# BT.net
KiCad netlist of a schematic drawn in Altium Designer
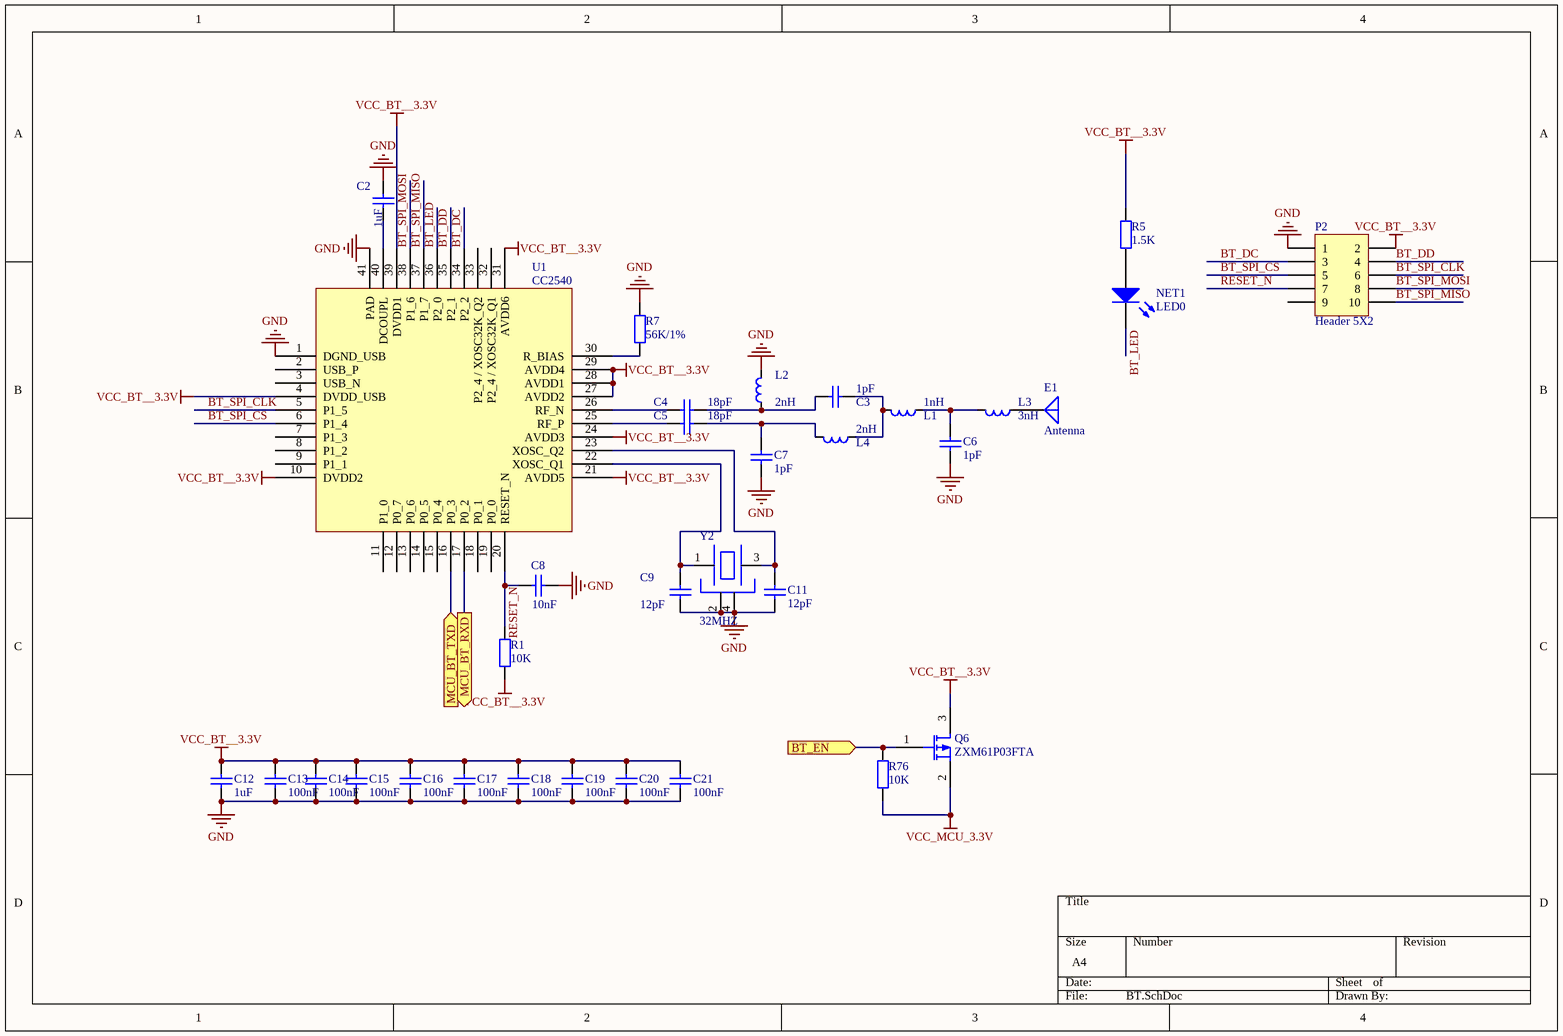
[diagram p0: BT.SchDoc]

(export (version "E")
  (design (tool "Eeschema 10.0.6"))
  (components
    (comp (ref "C2")
      (value "1uF")
      (footprint "0603C")
      (description "Capacitor")
      (fields (field (name "PUBLISHER") "Altium Limited"))
      (libsource (lib "Miscellaneous Devices") (part "Cap"))
    )
    (comp (ref "C3")
      (value "1pF")
      (footprint "0402C")
      (description "Capacitor")
      (fields (field (name "PUBLISHER") "Altium Limited"))
      (libsource (lib "Miscellaneous Devices") (part "Cap"))
    )
    (comp (ref "C4")
      (value "18pF")
      (footprint "0402C")
      (description "Capacitor")
      (fields (field (name "PUBLISHER") "Altium Limited"))
      (libsource (lib "Miscellaneous Devices") (part "Cap"))
    )
    (comp (ref "C5")
      (value "18pF")
      (footprint "0402C")
      (description "Capacitor")
      (fields (field (name "PUBLISHER") "Altium Limited"))
      (libsource (lib "Miscellaneous Devices") (part "Cap"))
    )
    (comp (ref "C6")
      (value "1pF")
      (footprint "0402C")
      (description "Capacitor")
      (fields (field (name "PUBLISHER") "Altium Limited"))
      (libsource (lib "Miscellaneous Devices") (part "Cap"))
    )
    (comp (ref "C7")
      (value "1pF")
      (footprint "0402C")
      (description "Capacitor")
      (fields (field (name "PUBLISHER") "Altium Limited"))
      (libsource (lib "Miscellaneous Devices") (part "Cap"))
    )
    (comp (ref "C8")
      (value "10nF")
      (footprint "0402C")
      (description "Capacitor")
      (fields (field (name "PUBLISHER") "Altium Limited"))
      (libsource (lib "Miscellaneous Devices") (part "Cap"))
    )
    (comp (ref "C9")
      (value "12pF")
      (footprint "0402C")
      (description "Capacitor")
      (fields (field (name "PUBLISHER") "Altium Limited"))
      (libsource (lib "Miscellaneous Devices") (part "Cap"))
    )
    (comp (ref "C11")
      (value "12pF")
      (footprint "0402C")
      (description "Capacitor")
      (fields (field (name "PUBLISHER") "Altium Limited"))
      (libsource (lib "Miscellaneous Devices") (part "Cap"))
    )
    (comp (ref "C12")
      (value "1uF")
      (footprint "0603C")
      (description "Capacitor")
      (fields (field (name "PUBLISHER") "Altium Limited"))
      (libsource (lib "Miscellaneous Devices") (part "Cap"))
    )
    (comp (ref "C13")
      (value "100nF")
      (footprint "0603C")
      (description "Capacitor")
      (fields (field (name "PUBLISHER") "Altium Limited"))
      (libsource (lib "Miscellaneous Devices") (part "Cap"))
    )
    (comp (ref "C14")
      (value "100nF")
      (footprint "0603C")
      (description "Capacitor")
      (fields (field (name "PUBLISHER") "Altium Limited"))
      (libsource (lib "Miscellaneous Devices") (part "Cap"))
    )
    (comp (ref "C15")
      (value "100nF")
      (footprint "0603C")
      (description "Capacitor")
      (fields (field (name "PUBLISHER") "Altium Limited"))
      (libsource (lib "Miscellaneous Devices") (part "Cap"))
    )
    (comp (ref "C16")
      (value "100nF")
      (footprint "0603C")
      (description "Capacitor")
      (fields (field (name "PUBLISHER") "Altium Limited"))
      (libsource (lib "Miscellaneous Devices") (part "Cap"))
    )
    (comp (ref "C17")
      (value "100nF")
      (footprint "0603C")
      (description "Capacitor")
      (fields (field (name "PUBLISHER") "Altium Limited"))
      (libsource (lib "Miscellaneous Devices") (part "Cap"))
    )
    (comp (ref "C18")
      (value "100nF")
      (footprint "0603C")
      (description "Capacitor")
      (fields (field (name "PUBLISHER") "Altium Limited"))
      (libsource (lib "Miscellaneous Devices") (part "Cap"))
    )
    (comp (ref "C19")
      (value "100nF")
      (footprint "0603C")
      (description "Capacitor")
      (fields (field (name "PUBLISHER") "Altium Limited"))
      (libsource (lib "Miscellaneous Devices") (part "Cap"))
    )
    (comp (ref "C20")
      (value "100nF")
      (footprint "0603C")
      (description "Capacitor")
      (fields (field (name "PUBLISHER") "Altium Limited"))
      (libsource (lib "Miscellaneous Devices") (part "Cap"))
    )
    (comp (ref "C21")
      (value "100nF")
      (footprint "0603C")
      (description "Capacitor")
      (fields (field (name "PUBLISHER") "Altium Limited"))
      (libsource (lib "Miscellaneous Devices") (part "Cap"))
    )
    (comp (ref "E1")
      (value "Antenna")
      (footprint "AN2051")
      (description "Generic Antenna")
      (fields (field (name "PUBLISHER") "Altium Limited"))
      (libsource (lib "Miscellaneous Devices") (part "Antenna"))
    )
    (comp (ref "L1") (value "1nH") (footprint "0402R") (description "L") (libsource (lib "") (part "L_4_1")))
    (comp (ref "L2") (value "2nH") (footprint "0402R") (description "L") (libsource (lib "*") (part "L_4")))
    (comp (ref "L3") (value "3nH") (footprint "0402R") (description "L") (libsource (lib "") (part "L_4_1")))
    (comp (ref "L4") (value "2nH") (footprint "0402R") (description "L") (libsource (lib "") (part "L_4_1")))
    (comp (ref "NET1")
      (value "LED0")
      (footprint "0603LED")
      (description "Typical INFRARED GaAs LED")
      (fields (field (name "PUBLISHER") "Altium Limited"))
      (libsource (lib "Miscellaneous Devices") (part "LED0"))
    )
    (comp (ref "P2")
      (value "Header 5X2")
      (footprint "HDR2X5")
      (description "Header, 5-Pin, Dual row")
      (fields (field (name "PUBLISHER") "Altium Limited"))
      (libsource (lib "Miscellaneous Connectors") (part "Header 5X2"))
    )
    (comp (ref "Q6")
      (value "ZXM61P03FTA")
      (footprint "SOT23-3")
      (description "ZXM61P03F")
      (fields (field (name "PUBLISHER") "Altium Limited"))
      (libsource (lib "Miscellaneous Devices") (part "MOSFET-P"))
    )
    (comp (ref "R1")
      (value "10K")
      (footprint "0603R")
      (description "Resistor")
      (fields (field (name "PUBLISHER") "Altium Limited"))
      (libsource (lib "Miscellaneous Devices") (part "Res2"))
    )
    (comp (ref "R5")
      (value "1.5K")
      (footprint "0603R")
      (description "Resistor")
      (fields (field (name "PUBLISHER") "Altium Limited"))
      (libsource (lib "Miscellaneous Devices") (part "Res2"))
    )
    (comp (ref "R7")
      (value "56K/1%")
      (footprint "0603R")
      (description "Resistor")
      (fields (field (name "PUBLISHER") "Altium Limited"))
      (libsource (lib "Miscellaneous Devices") (part "Res2"))
    )
    (comp (ref "R76")
      (value "10K")
      (footprint "0603R")
      (description "Resistor")
      (fields (field (name "PUBLISHER") "Altium Limited"))
      (libsource (lib "Miscellaneous Devices") (part "Res2"))
    )
    (comp (ref "U1")
      (value "CC2540")
      (footprint "QFN50P600X600X80-40N")
      (libsource (lib "stm32") (part "CC2540"))
    )
    (comp (ref "Y2")
      (value "32MHZ")
      (footprint "OSCILLATOR-3.2X2.5")
      (libsource (lib "Myself_1") (part "XTAL3"))
    )
  )
  (nets
    (net (code "1") (name "/BT_DC") (class "Default")
      (node (ref "P2") (pin "3") (pinfunction "3_3") (pintype "passive"))
      (node (ref "U1") (pin "34") (pinfunction "P2_2_34") (pintype "passive"))
    )
    (net (code "2") (name "/BT_DD") (class "Default")
      (node (ref "P2") (pin "4") (pinfunction "4_4") (pintype "passive"))
      (node (ref "U1") (pin "35") (pinfunction "P2_1_35") (pintype "passive"))
    )
    (net (code "3") (name "/BT_EN") (class "Default")
      (node (ref "Q6") (pin "1") (pinfunction "G_1") (pintype "passive"))
      (node (ref "R76") (pin "1") (pinfunction "1_1") (pintype "passive"))
    )
    (net (code "4") (name "/BT_LED") (class "Default")
      (node (ref "NET1") (pin "2") (pinfunction "K_2") (pintype "passive"))
      (node (ref "U1") (pin "36") (pinfunction "P2_0_36") (pintype "passive"))
    )
    (net (code "5") (name "/BT_SPI_CLK") (class "Default")
      (node (ref "P2") (pin "6") (pinfunction "6_6") (pintype "passive"))
      (node (ref "U1") (pin "5") (pinfunction "P1_5_5") (pintype "passive"))
    )
    (net (code "6") (name "/BT_SPI_CS") (class "Default")
      (node (ref "P2") (pin "5") (pinfunction "5_5") (pintype "passive"))
      (node (ref "U1") (pin "6") (pinfunction "P1_4_6") (pintype "passive"))
    )
    (net (code "7") (name "/BT_SPI_MISO") (class "Default")
      (node (ref "P2") (pin "10") (pinfunction "10_10") (pintype "passive"))
      (node (ref "U1") (pin "37") (pinfunction "P1_7_37") (pintype "passive"))
    )
    (net (code "8") (name "/BT_SPI_MOSI") (class "Default")
      (node (ref "P2") (pin "8") (pinfunction "8_8") (pintype "passive"))
      (node (ref "U1") (pin "38") (pinfunction "P1_6_38") (pintype "passive"))
    )
    (net (code "9") (name "/MCU_BT_RXD") (class "Default")
      (node (ref "U1") (pin "17") (pinfunction "P0_2_17") (pintype "passive"))
    )
    (net (code "10") (name "/MCU_BT_TXD") (class "Default")
      (node (ref "U1") (pin "16") (pinfunction "P0_3_16") (pintype "passive"))
    )
    (net (code "11") (name "/RESET_N") (class "Default")
      (node (ref "C8") (pin "2") (pinfunction "2_2") (pintype "passive"))
      (node (ref "P2") (pin "7") (pinfunction "7_7") (pintype "passive"))
      (node (ref "R1") (pin "1") (pinfunction "1_1") (pintype "passive"))
      (node (ref "U1") (pin "20") (pinfunction "RESET_N_20") (pintype "passive"))
    )
    (net (code "12") (name "GND") (class "Default")
      (node (ref "C11") (pin "1") (pinfunction "1_1") (pintype "passive"))
      (node (ref "C12") (pin "2") (pinfunction "2_2") (pintype "passive"))
      (node (ref "C13") (pin "2") (pinfunction "2_2") (pintype "passive"))
      (node (ref "C14") (pin "2") (pinfunction "2_2") (pintype "passive"))
      (node (ref "C15") (pin "2") (pinfunction "2_2") (pintype "passive"))
      (node (ref "C16") (pin "2") (pinfunction "2_2") (pintype "passive"))
      (node (ref "C17") (pin "2") (pinfunction "2_2") (pintype "passive"))
      (node (ref "C18") (pin "2") (pinfunction "2_2") (pintype "passive"))
      (node (ref "C19") (pin "2") (pinfunction "2_2") (pintype "passive"))
      (node (ref "C2") (pin "1") (pinfunction "1_1") (pintype "passive"))
      (node (ref "C20") (pin "2") (pinfunction "2_2") (pintype "passive"))
      (node (ref "C21") (pin "2") (pinfunction "2_2") (pintype "passive"))
      (node (ref "C6") (pin "1") (pinfunction "1_1") (pintype "passive"))
      (node (ref "C7") (pin "1") (pinfunction "1_1") (pintype "passive"))
      (node (ref "C8") (pin "1") (pinfunction "1_1") (pintype "passive"))
      (node (ref "C9") (pin "1") (pinfunction "1_1") (pintype "passive"))
      (node (ref "L2") (pin "2") (pintype "passive"))
      (node (ref "P2") (pin "1") (pinfunction "1_1") (pintype "passive"))
      (node (ref "R7") (pin "1") (pinfunction "1_1") (pintype "passive"))
      (node (ref "U1") (pin "1") (pinfunction "DGND_USB_1") (pintype "passive"))
      (node (ref "U1") (pin "41") (pinfunction "PAD_41") (pintype "passive"))
      (node (ref "Y2") (pin "2") (pinfunction "GND_2") (pintype "passive"))
      (node (ref "Y2") (pin "4") (pinfunction "GND_4") (pintype "passive"))
    )
    (net (code "13") (name "Net-(C3-Pad1)") (class "Default")
      (node (ref "C3") (pin "1") (pinfunction "1_1") (pintype "passive"))
      (node (ref "C4") (pin "2") (pinfunction "2_2") (pintype "passive"))
      (node (ref "L2") (pin "1") (pintype "passive"))
    )
    (net (code "14") (name "Net-(C3-Pad2)") (class "Default")
      (node (ref "C3") (pin "2") (pinfunction "2_2") (pintype "passive"))
      (node (ref "L1") (pin "2") (pintype "passive"))
      (node (ref "L4") (pin "1") (pintype "passive"))
    )
    (net (code "15") (name "Net-(C5-Pad2)") (class "Default")
      (node (ref "C5") (pin "2") (pinfunction "2_2") (pintype "passive"))
      (node (ref "C7") (pin "2") (pinfunction "2_2") (pintype "passive"))
      (node (ref "L4") (pin "2") (pintype "passive"))
    )
    (net (code "16") (name "Net-(C6-Pad2)") (class "Default")
      (node (ref "C6") (pin "2") (pinfunction "2_2") (pintype "passive"))
      (node (ref "L1") (pin "1") (pintype "passive"))
      (node (ref "L3") (pin "2") (pintype "passive"))
    )
    (net (code "17") (name "Net-(E1-A)") (class "Default")
      (node (ref "E1") (pin "1") (pinfunction "A_1") (pintype "passive"))
      (node (ref "L3") (pin "1") (pintype "passive"))
    )
    (net (code "18") (name "Net-(NET1-A)") (class "Default")
      (node (ref "NET1") (pin "1") (pinfunction "A_1") (pintype "passive"))
      (node (ref "R5") (pin "2") (pinfunction "2_2") (pintype "passive"))
    )
    (net (code "19") (name "Net-(U1-DCOUPL)") (class "Default")
      (node (ref "C2") (pin "2") (pinfunction "2_2") (pintype "passive"))
      (node (ref "U1") (pin "40") (pinfunction "DCOUPL_40") (pintype "passive"))
    )
    (net (code "20") (name "Net-(U1-RF_N)") (class "Default")
      (node (ref "C4") (pin "1") (pinfunction "1_1") (pintype "passive"))
      (node (ref "U1") (pin "26") (pinfunction "RF_N_26") (pintype "passive"))
    )
    (net (code "21") (name "Net-(U1-RF_P)") (class "Default")
      (node (ref "C5") (pin "1") (pinfunction "1_1") (pintype "passive"))
      (node (ref "U1") (pin "25") (pinfunction "RF_P_25") (pintype "passive"))
    )
    (net (code "22") (name "Net-(U1-R_BIAS)") (class "Default")
      (node (ref "R7") (pin "2") (pinfunction "2_2") (pintype "passive"))
      (node (ref "U1") (pin "30") (pinfunction "R_BIAS_30") (pintype "passive"))
    )
    (net (code "23") (name "Net-(U1-XOSC_Q1)") (class "Default")
      (node (ref "C9") (pin "2") (pinfunction "2_2") (pintype "passive"))
      (node (ref "U1") (pin "22") (pinfunction "XOSC_Q1_22") (pintype "passive"))
      (node (ref "Y2") (pin "1") (pinfunction "1_1") (pintype "passive"))
    )
    (net (code "24") (name "Net-(U1-XOSC_Q2)") (class "Default")
      (node (ref "C11") (pin "2") (pinfunction "2_2") (pintype "passive"))
      (node (ref "U1") (pin "23") (pinfunction "XOSC_Q2_23") (pintype "passive"))
      (node (ref "Y2") (pin "3") (pinfunction "3_3") (pintype "passive"))
    )
    (net (code "25") (name "VCC_BT__3.3V") (class "Default")
      (node (ref "C12") (pin "1") (pinfunction "1_1") (pintype "passive"))
      (node (ref "C13") (pin "1") (pinfunction "1_1") (pintype "passive"))
      (node (ref "C14") (pin "1") (pinfunction "1_1") (pintype "passive"))
      (node (ref "C15") (pin "1") (pinfunction "1_1") (pintype "passive"))
      (node (ref "C16") (pin "1") (pinfunction "1_1") (pintype "passive"))
      (node (ref "C17") (pin "1") (pinfunction "1_1") (pintype "passive"))
      (node (ref "C18") (pin "1") (pinfunction "1_1") (pintype "passive"))
      (node (ref "C19") (pin "1") (pinfunction "1_1") (pintype "passive"))
      (node (ref "C20") (pin "1") (pinfunction "1_1") (pintype "passive"))
      (node (ref "C21") (pin "1") (pinfunction "1_1") (pintype "passive"))
      (node (ref "P2") (pin "2") (pinfunction "2_2") (pintype "passive"))
      (node (ref "Q6") (pin "3") (pinfunction "S_3") (pintype "passive"))
      (node (ref "R1") (pin "2") (pinfunction "2_2") (pintype "passive"))
      (node (ref "R5") (pin "1") (pinfunction "1_1") (pintype "passive"))
      (node (ref "U1") (pin "10") (pinfunction "DVDD2_10") (pintype "passive"))
      (node (ref "U1") (pin "21") (pinfunction "AVDD5_21") (pintype "passive"))
      (node (ref "U1") (pin "24") (pinfunction "AVDD3_24") (pintype "passive"))
      (node (ref "U1") (pin "27") (pinfunction "AVDD2_27") (pintype "passive"))
      (node (ref "U1") (pin "28") (pinfunction "AVDD1_28") (pintype "passive"))
      (node (ref "U1") (pin "29") (pinfunction "AVDD4_29") (pintype "passive"))
      (node (ref "U1") (pin "31") (pinfunction "AVDD6_31") (pintype "passive"))
      (node (ref "U1") (pin "39") (pinfunction "DVDD1_39") (pintype "passive"))
      (node (ref "U1") (pin "4") (pinfunction "DVDD_USB_4") (pintype "passive"))
    )
    (net (code "26") (name "VCC_MCU_3.3V") (class "Default")
      (node (ref "Q6") (pin "2") (pinfunction "D_2") (pintype "passive"))
      (node (ref "R76") (pin "2") (pinfunction "2_2") (pintype "passive"))
    )
    (net (code "27") (name "unconnected-(P2-Pad9)") (class "Default")
      (node (ref "P2") (pin "9") (pinfunction "9_9") (pintype "passive"))
    )
    (net (code "28") (name "unconnected-(U1-P0_0-Pad19)") (class "Default")
      (node (ref "U1") (pin "19") (pinfunction "P0_0_19") (pintype "passive"))
    )
    (net (code "29") (name "unconnected-(U1-P0_1-Pad18)") (class "Default")
      (node (ref "U1") (pin "18") (pinfunction "P0_1_18") (pintype "passive"))
    )
    (net (code "30") (name "unconnected-(U1-P0_4-Pad15)") (class "Default")
      (node (ref "U1") (pin "15") (pinfunction "P0_4_15") (pintype "passive"))
    )
    (net (code "31") (name "unconnected-(U1-P0_5-Pad14)") (class "Default")
      (node (ref "U1") (pin "14") (pinfunction "P0_5_14") (pintype "passive"))
    )
    (net (code "32") (name "unconnected-(U1-P0_6-Pad13)") (class "Default")
      (node (ref "U1") (pin "13") (pinfunction "P0_6_13") (pintype "passive"))
    )
    (net (code "33") (name "unconnected-(U1-P0_7-Pad12)") (class "Default")
      (node (ref "U1") (pin "12") (pinfunction "P0_7_12") (pintype "passive"))
    )
    (net (code "34") (name "unconnected-(U1-P1_0-Pad11)") (class "Default")
      (node (ref "U1") (pin "11") (pinfunction "P1_0_11") (pintype "passive"))
    )
    (net (code "35") (name "unconnected-(U1-P1_1-Pad9)") (class "Default")
      (node (ref "U1") (pin "9") (pinfunction "P1_1_9") (pintype "passive"))
    )
    (net (code "36") (name "unconnected-(U1-P1_2-Pad8)") (class "Default")
      (node (ref "U1") (pin "8") (pinfunction "P1_2_8") (pintype "passive"))
    )
    (net (code "37") (name "unconnected-(U1-P1_3-Pad7)") (class "Default")
      (node (ref "U1") (pin "7") (pinfunction "P1_3_7") (pintype "passive"))
    )
    (net (code "38") (name "unconnected-(U1-P2_4_{slash}_XOSC32K_Q1-Pad32)") (class "Default")
      (node (ref "U1") (pin "32") (pinfunction "P2_4_/_XOSC32K_Q1_32") (pintype "passive"))
    )
    (net (code "39") (name "unconnected-(U1-P2_4_{slash}_XOSC32K_Q2-Pad33)") (class "Default")
      (node (ref "U1") (pin "33") (pinfunction "P2_4_/_XOSC32K_Q2_33") (pintype "passive"))
    )
    (net (code "40") (name "unconnected-(U1-USB_N-Pad3)") (class "Default")
      (node (ref "U1") (pin "3") (pinfunction "USB_N_3") (pintype "passive"))
    )
    (net (code "41") (name "unconnected-(U1-USB_P-Pad2)") (class "Default")
      (node (ref "U1") (pin "2") (pinfunction "USB_P_2") (pintype "passive"))
    )
  )
)
